# CC3000.net
KiCad netlist of a schematic drawn in Altium Designer
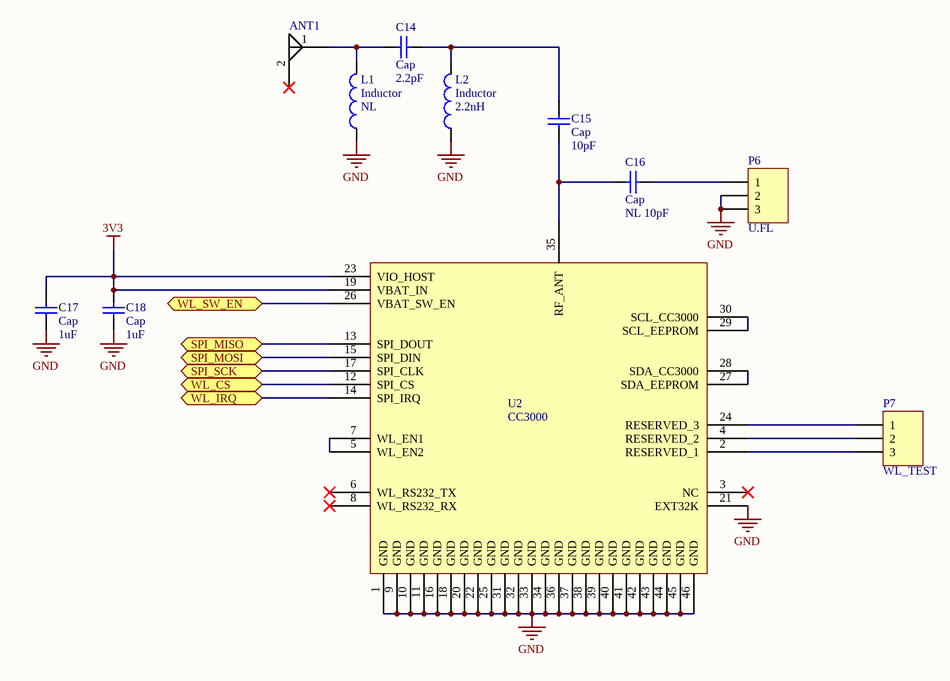
[diagram p0: CC3000.SchDoc]

(export (version "E")
  (design (tool "Eeschema 10.0.6"))
  (components
    (comp (ref "ANT1")
      (value "ANT-SMT-2")
      (footprint "2500AT44M0400")
      (libsource (lib "BrewBit") (part "ANT-SMT-2"))
    )
    (comp (ref "C14")
      (value "Cap")
      (description "Capacitor")
      (fields (field (name "ALTIUM_VALUE") "2.2pF"))
      (libsource (lib "Miscellaneous Devices") (part "Cap"))
    )
    (comp (ref "C15")
      (value "Cap")
      (description "Capacitor")
      (fields (field (name "ALTIUM_VALUE") "10pF"))
      (libsource (lib "Miscellaneous Devices") (part "Cap"))
    )
    (comp (ref "C16")
      (value "Cap")
      (description "Capacitor")
      (fields (field (name "ALTIUM_VALUE") "NL 10pF"))
      (libsource (lib "Miscellaneous Devices") (part "Cap"))
    )
    (comp (ref "C17")
      (value "Cap")
      (footprint "RAD-0.3")
      (description "Capacitor")
      (fields (field (name "ALTIUM_VALUE") "1uF"))
      (libsource (lib "Miscellaneous Devices") (part "Cap"))
    )
    (comp (ref "C18")
      (value "Cap")
      (footprint "RAD-0.3")
      (description "Capacitor")
      (fields (field (name "ALTIUM_VALUE") "1uF"))
      (libsource (lib "Miscellaneous Devices") (part "Cap"))
    )
    (comp (ref "L1")
      (value "Inductor")
      (footprint "0402-A")
      (fields (field (name "ALTIUM_VALUE") "NL"))
      (libsource (lib "Miscellaneous Devices") (part "Inductor"))
    )
    (comp (ref "L2")
      (value "Inductor")
      (footprint "0402-A")
      (fields (field (name "ALTIUM_VALUE") "2.2nH"))
      (libsource (lib "Miscellaneous Devices") (part "Inductor"))
    )
    (comp (ref "P6")
      (value "U.FL")
      (footprint "HDR1X3")
      (description "Header, 3-Pin")
      (libsource (lib "Miscellaneous Connectors") (part "Header 3"))
    )
    (comp (ref "P7")
      (value "WL_TEST")
      (footprint "HDR1X3")
      (description "Header, 3-Pin")
      (libsource (lib "Miscellaneous Connectors") (part "Header 3"))
    )
    (comp (ref "U2")
      (value "CC3000")
      (footprint "CC3000")
      (description "CC3000 WLAN Module")
      (libsource (lib "BrewBit") (part "CC3000"))
    )
  )
  (nets
    (net (code "1") (name "/SPI_MISO") (class "Default")
      (node (ref "U2") (pin "13") (pinfunction "SPI_DOUT_13") (pintype "passive"))
    )
    (net (code "2") (name "/SPI_MOSI") (class "Default")
      (node (ref "U2") (pin "15") (pinfunction "SPI_DIN_15") (pintype "passive"))
    )
    (net (code "3") (name "/SPI_SCK") (class "Default")
      (node (ref "U2") (pin "17") (pinfunction "SPI_CLK_17") (pintype "passive"))
    )
    (net (code "4") (name "/WL_CS") (class "Default")
      (node (ref "U2") (pin "12") (pinfunction "SPI_CS_12") (pintype "passive"))
    )
    (net (code "5") (name "/WL_IRQ") (class "Default")
      (node (ref "U2") (pin "14") (pinfunction "SPI_IRQ_14") (pintype "passive"))
    )
    (net (code "6") (name "/WL_SW_EN") (class "Default")
      (node (ref "U2") (pin "26") (pinfunction "VBAT_SW_EN_26") (pintype "passive"))
    )
    (net (code "7") (name "3V3") (class "Default")
      (node (ref "C17") (pin "2") (pinfunction "2_2") (pintype "passive"))
      (node (ref "C18") (pin "2") (pinfunction "2_2") (pintype "passive"))
      (node (ref "U2") (pin "19") (pinfunction "VBAT_IN_19") (pintype "passive"))
      (node (ref "U2") (pin "23") (pinfunction "VIO_HOST_23") (pintype "passive"))
    )
    (net (code "8") (name "GND") (class "Default")
      (node (ref "C17") (pin "1") (pinfunction "1_1") (pintype "passive"))
      (node (ref "C18") (pin "1") (pinfunction "1_1") (pintype "passive"))
      (node (ref "L1") (pin "1") (pinfunction "1_1") (pintype "passive"))
      (node (ref "L2") (pin "1") (pinfunction "1_1") (pintype "passive"))
      (node (ref "P6") (pin "2") (pinfunction "2_2") (pintype "passive"))
      (node (ref "P6") (pin "3") (pinfunction "3_3") (pintype "passive"))
      (node (ref "U2") (pin "1") (pinfunction "GND_1") (pintype "passive"))
      (node (ref "U2") (pin "10") (pinfunction "GND_10") (pintype "passive"))
      (node (ref "U2") (pin "11") (pinfunction "GND_11") (pintype "passive"))
      (node (ref "U2") (pin "16") (pinfunction "GND_16") (pintype "passive"))
      (node (ref "U2") (pin "18") (pinfunction "GND_18") (pintype "passive"))
      (node (ref "U2") (pin "20") (pinfunction "GND_20") (pintype "passive"))
      (node (ref "U2") (pin "21") (pinfunction "EXT32K_21") (pintype "passive"))
      (node (ref "U2") (pin "22") (pinfunction "GND_22") (pintype "passive"))
      (node (ref "U2") (pin "25") (pinfunction "GND_25") (pintype "passive"))
      (node (ref "U2") (pin "31") (pinfunction "GND_31") (pintype "passive"))
      (node (ref "U2") (pin "32") (pinfunction "GND_32") (pintype "passive"))
      (node (ref "U2") (pin "33") (pinfunction "GND_33") (pintype "passive"))
      (node (ref "U2") (pin "34") (pinfunction "GND_34") (pintype "passive"))
      (node (ref "U2") (pin "36") (pinfunction "GND_36") (pintype "passive"))
      (node (ref "U2") (pin "37") (pinfunction "GND_37") (pintype "passive"))
      (node (ref "U2") (pin "38") (pinfunction "GND_38") (pintype "passive"))
      (node (ref "U2") (pin "39") (pinfunction "GND_39") (pintype "passive"))
      (node (ref "U2") (pin "40") (pinfunction "GND_40") (pintype "passive"))
      (node (ref "U2") (pin "41") (pinfunction "GND_41") (pintype "passive"))
      (node (ref "U2") (pin "42") (pinfunction "GND_42") (pintype "passive"))
      (node (ref "U2") (pin "43") (pinfunction "GND_43") (pintype "passive"))
      (node (ref "U2") (pin "44") (pinfunction "GND_44") (pintype "passive"))
      (node (ref "U2") (pin "45") (pinfunction "GND_45") (pintype "passive"))
      (node (ref "U2") (pin "46") (pinfunction "GND_46") (pintype "passive"))
      (node (ref "U2") (pin "9") (pinfunction "GND_9") (pintype "passive"))
    )
    (net (code "9") (name "Net-(ANT1-Pad1)") (class "Default")
      (node (ref "ANT1") (pin "1") (pintype "passive"))
      (node (ref "C14") (pin "1") (pinfunction "1_1") (pintype "passive"))
      (node (ref "L1") (pin "2") (pinfunction "2_2") (pintype "passive"))
    )
    (net (code "10") (name "Net-(C14-Pad2)") (class "Default")
      (node (ref "C14") (pin "2") (pinfunction "2_2") (pintype "passive"))
      (node (ref "C15") (pin "2") (pinfunction "2_2") (pintype "passive"))
      (node (ref "L2") (pin "2") (pinfunction "2_2") (pintype "passive"))
    )
    (net (code "11") (name "Net-(C16-Pad1)") (class "Default")
      (node (ref "C16") (pin "1") (pinfunction "1_1") (pintype "passive"))
      (node (ref "P6") (pin "1") (pinfunction "1_1") (pintype "passive"))
    )
    (net (code "12") (name "Net-(U2-RESERVED_1)") (class "Default")
      (node (ref "P7") (pin "3") (pinfunction "3_3") (pintype "passive"))
      (node (ref "U2") (pin "2") (pinfunction "RESERVED_1_2") (pintype "passive"))
    )
    (net (code "13") (name "Net-(U2-RESERVED_2)") (class "Default")
      (node (ref "P7") (pin "2") (pinfunction "2_2") (pintype "passive"))
      (node (ref "U2") (pin "4") (pinfunction "RESERVED_2_4") (pintype "passive"))
    )
    (net (code "14") (name "Net-(U2-RESERVED_3)") (class "Default")
      (node (ref "P7") (pin "1") (pinfunction "1_1") (pintype "passive"))
      (node (ref "U2") (pin "24") (pinfunction "RESERVED_3_24") (pintype "passive"))
    )
    (net (code "15") (name "Net-(U2-RF_ANT)") (class "Default")
      (node (ref "C15") (pin "1") (pinfunction "1_1") (pintype "passive"))
      (node (ref "C16") (pin "2") (pinfunction "2_2") (pintype "passive"))
      (node (ref "U2") (pin "35") (pinfunction "RF_ANT_35") (pintype "passive"))
    )
    (net (code "16") (name "Net-(U2-SCL_CC3000)") (class "Default")
      (node (ref "U2") (pin "29") (pinfunction "SCL_EEPROM_29") (pintype "passive"))
      (node (ref "U2") (pin "30") (pinfunction "SCL_CC3000_30") (pintype "passive"))
    )
    (net (code "17") (name "Net-(U2-SDA_CC3000)") (class "Default")
      (node (ref "U2") (pin "27") (pinfunction "SDA_EEPROM_27") (pintype "passive"))
      (node (ref "U2") (pin "28") (pinfunction "SDA_CC3000_28") (pintype "passive"))
    )
    (net (code "18") (name "Net-(U2-WL_EN1)") (class "Default")
      (node (ref "U2") (pin "5") (pinfunction "WL_EN2_5") (pintype "passive"))
      (node (ref "U2") (pin "7") (pinfunction "WL_EN1_7") (pintype "passive"))
    )
    (net (code "19") (name "unconnected-(ANT1-Pad2)") (class "Default")
      (node (ref "ANT1") (pin "2") (pintype "passive+no_connect"))
    )
    (net (code "20") (name "unconnected-(U2-NC-Pad3)") (class "Default")
      (node (ref "U2") (pin "3") (pinfunction "NC_3") (pintype "passive+no_connect"))
    )
    (net (code "21") (name "unconnected-(U2-WL_RS232_RX-Pad8)") (class "Default")
      (node (ref "U2") (pin "8") (pinfunction "WL_RS232_RX_8") (pintype "passive+no_connect"))
    )
    (net (code "22") (name "unconnected-(U2-WL_RS232_TX-Pad6)") (class "Default")
      (node (ref "U2") (pin "6") (pinfunction "WL_RS232_TX_6") (pintype "passive+no_connect"))
    )
  )
)
